# TSSI.net
KiCad netlist of a schematic drawn in Altium Designer
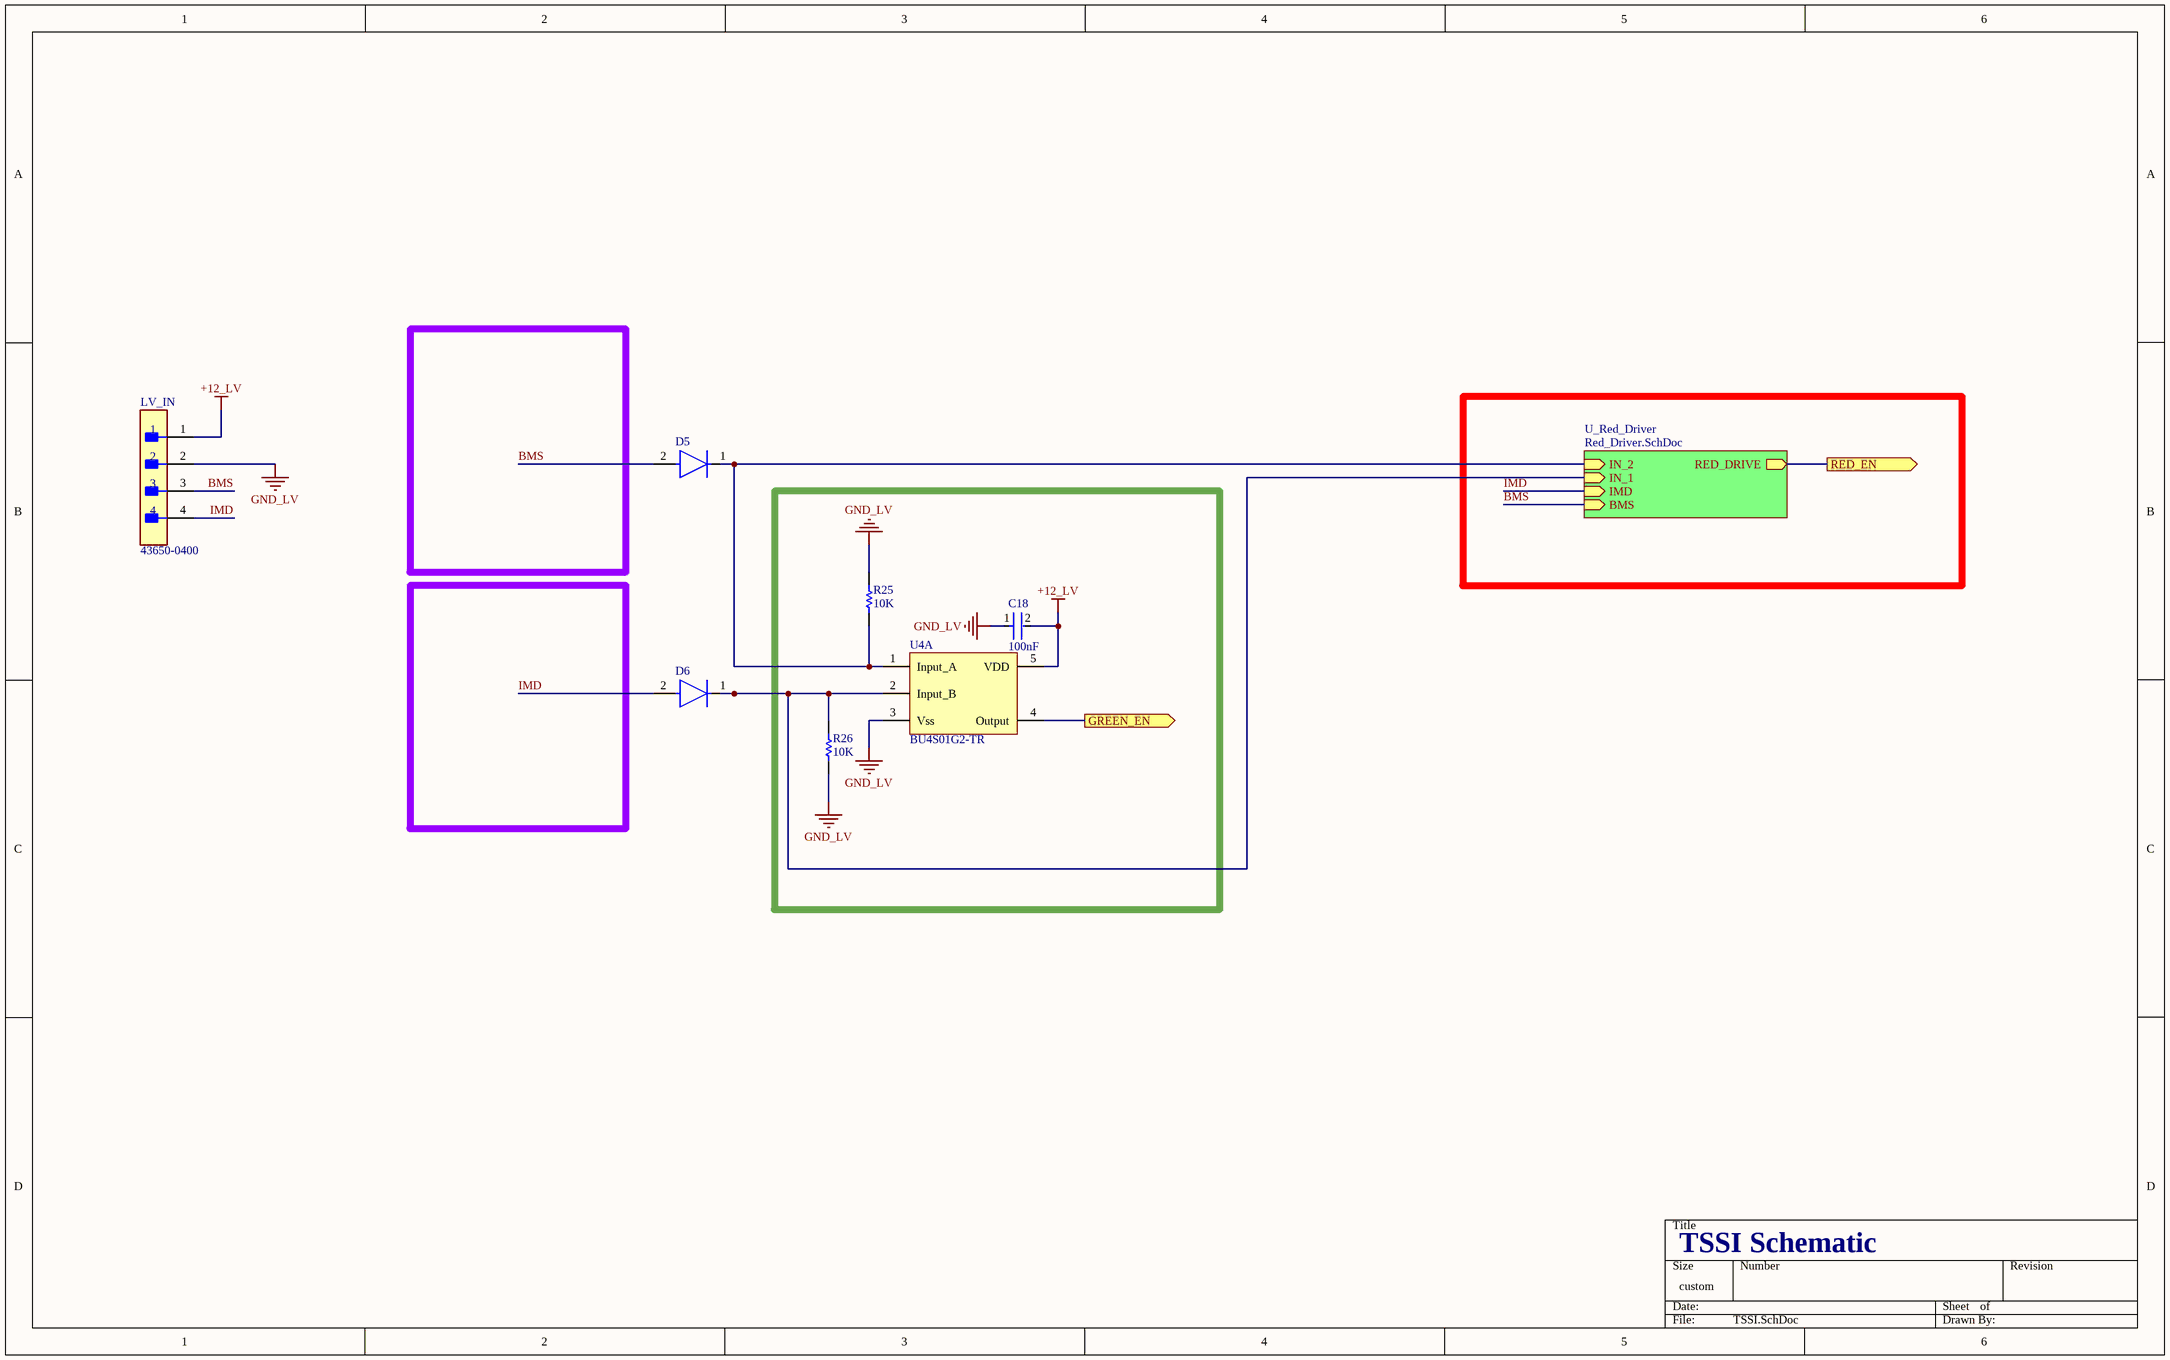
[diagram p0: TSSI.SchDoc]

(export (version "E")
  (design (tool "Eeschema 10.0.6"))
  (components
    (comp (ref "C18")
      (value "100nF")
      (footprint "FP-C1206C-EB-MFG")
      (description "CAP CER 0.1UF 100V X7R 1206")
      (fields
        (field (name "TOLERANCE") "0.1")
        (field (name "OCTOPART") "https://octopart.com/c1206c104k1ractu-kemet-89521")
      )
      (libsource (lib "Altium Content Vault") (part "b4654b650e69147ec39a6b967a45e02"))
    )
    (comp (ref "D5")
      (value "DO-204AH_8_CENTRALSEMI_1")
      (footprint "FP-JANTXV1N486B-MFG")
      (description "Diode 250 V 200mA Through Hole DO-35")
      (libsource (lib "Ontario Tech Racing New") (part "d7152d700b627762746794eb795d46e"))
    )
    (comp (ref "D6")
      (value "DO-204AH_8_CENTRALSEMI_1")
      (footprint "FP-JANTXV1N486B-MFG")
      (description "Diode 250 V 200mA Through Hole DO-35")
      (libsource (lib "Ontario Tech Racing New") (part "d7152d700b627762746794eb795d46e"))
    )
    (comp (ref "LV_IN")
      (value "43650-0400")
      (footprint "FP-0436500400-MFG")
      (description "43650-0400 Connector Wire to Board Header 4 Position 3mm Solder Right Angle Thru-Hole Tray")
      (libsource (lib "Altium Content Vault") (part "299a8cea1bdcbc3624fe62c390fa72c"))
    )
    (comp (ref "R25")
      (value "10K")
      (footprint "R_1206_YAGEO_AC")
      (description "RES SMD 10K OHM 1% 1/4W 1206")
      (fields (field (name "MANUFACTURER") "YAGEO") (field (name "TOLERANCE") "1%"))
      (libsource (lib "Ontario Tech Racing New") (part "resistor-1"))
    )
    (comp (ref "R26")
      (value "10K")
      (footprint "R_1206_YAGEO_AC")
      (description "RES SMD 10K OHM 1% 1/4W 1206")
      (fields (field (name "MANUFACTURER") "YAGEO") (field (name "TOLERANCE") "1%"))
      (libsource (lib "Ontario Tech Racing New") (part "resistor-1"))
    )
    (comp (ref "U4")
      (value "BU4S01G2-TR")
      (footprint "SOT23__ROHM_SEMICONDUCTOR_TSZ02201")
      (description "NOR Gate IC 1 Channel 5-SSOP")
      (fields (field (name "MANUFACTURER") "Rohm Semiconductor"))
      (libsource (lib "Ontario Tech Racing New") (part "BU4S01G2-TR"))
    )
  )
  (nets
    (net (code "1") (name "+12_LV") (class "Default")
      (node (ref "C18") (pin "2") (pinfunction "2_2") (pintype "passive"))
      (node (ref "LV_IN") (pin "1") (pinfunction "1_1") (pintype "passive"))
      (node (ref "U4") (pin "5") (pinfunction "VDD_5") (pintype "passive"))
    )
    (net (code "2") (name "/BMS") (class "Default")
      (node (ref "D5") (pin "2") (pinfunction "A_2") (pintype "passive"))
      (node (ref "LV_IN") (pin "3") (pinfunction "3_3") (pintype "passive"))
    )
    (net (code "3") (name "/GREEN_EN") (class "Default")
      (node (ref "U4") (pin "4") (pinfunction "Output_4") (pintype "passive"))
    )
    (net (code "4") (name "/IMD") (class "Default")
      (node (ref "D6") (pin "2") (pinfunction "A_2") (pintype "passive"))
      (node (ref "LV_IN") (pin "4") (pinfunction "4_4") (pintype "passive"))
    )
    (net (code "5") (name "/IN_1") (class "Default")
      (node (ref "D6") (pin "1") (pinfunction "C_1") (pintype "passive"))
      (node (ref "R26") (pin "1") (pinfunction "1_1") (pintype "passive"))
      (node (ref "U4") (pin "2") (pinfunction "Input_B_2") (pintype "passive"))
    )
    (net (code "6") (name "/IN_2") (class "Default")
      (node (ref "D5") (pin "1") (pinfunction "C_1") (pintype "passive"))
      (node (ref "R25") (pin "2") (pinfunction "2_2") (pintype "passive"))
      (node (ref "U4") (pin "1") (pinfunction "Input_A_1") (pintype "passive"))
    )
    (net (code "8") (name "GND_LV") (class "Default")
      (node (ref "C18") (pin "1") (pinfunction "1_1") (pintype "passive"))
      (node (ref "LV_IN") (pin "2") (pinfunction "2_2") (pintype "passive"))
      (node (ref "R25") (pin "1") (pinfunction "1_1") (pintype "passive"))
      (node (ref "R26") (pin "2") (pinfunction "2_2") (pintype "passive"))
      (node (ref "U4") (pin "3") (pinfunction "Vss_3") (pintype "passive"))
    )
  )
)
